# P09_USB_HOST_USB_OTG.net
KiCad netlist of a schematic drawn in Altium Designer
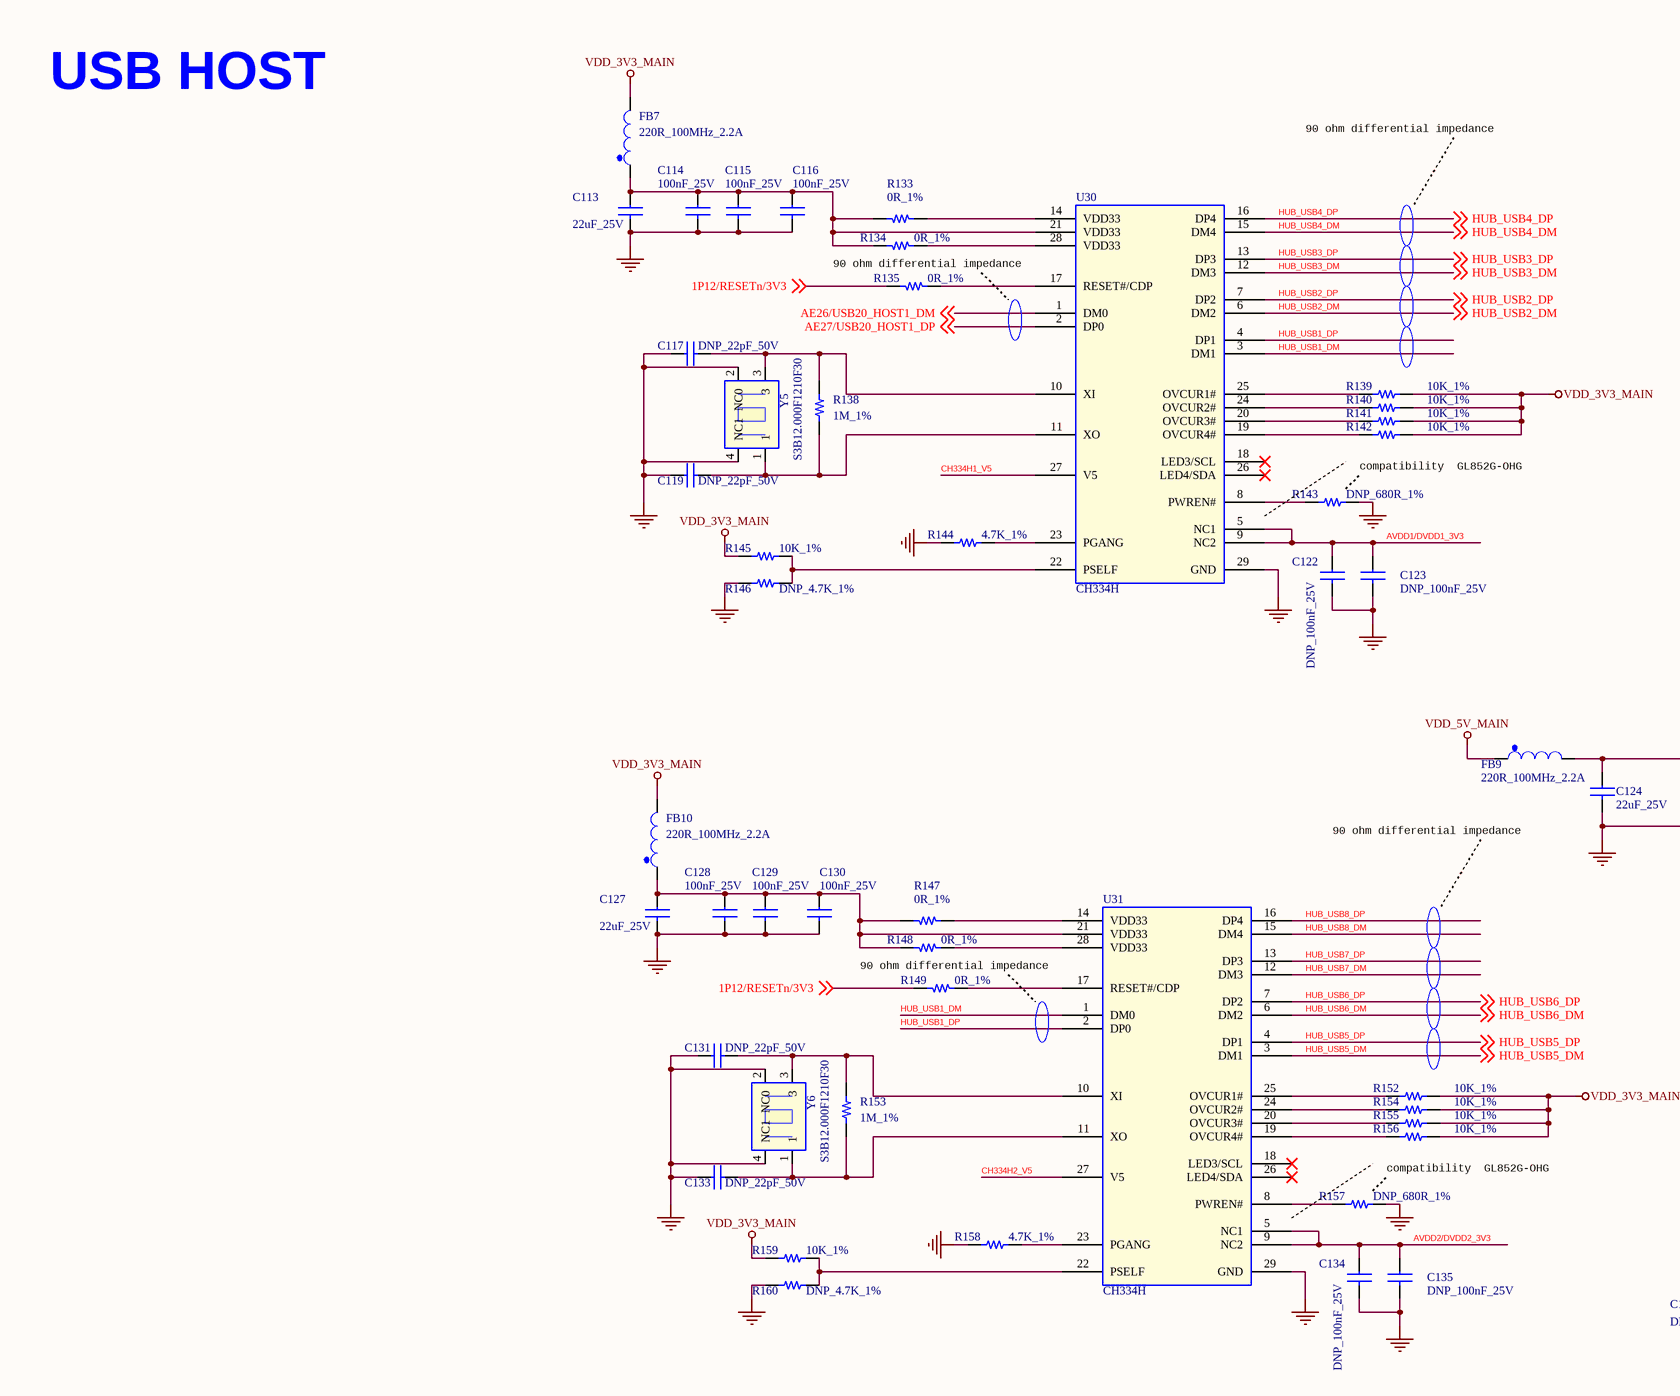
[diagram p0: P09_USB HOST_USB OTG.SchDoc, top left]
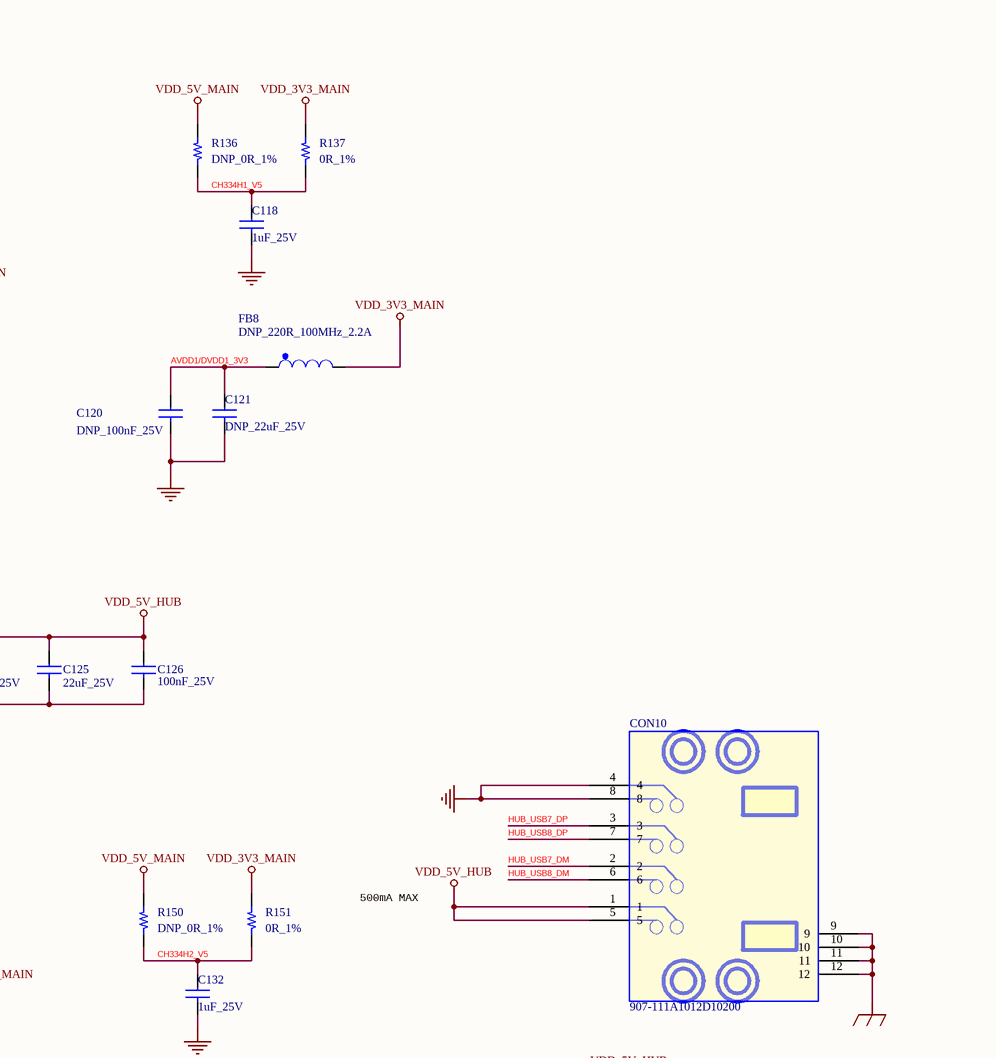
[diagram p1: P09_USB HOST_USB OTG.SchDoc, top right]
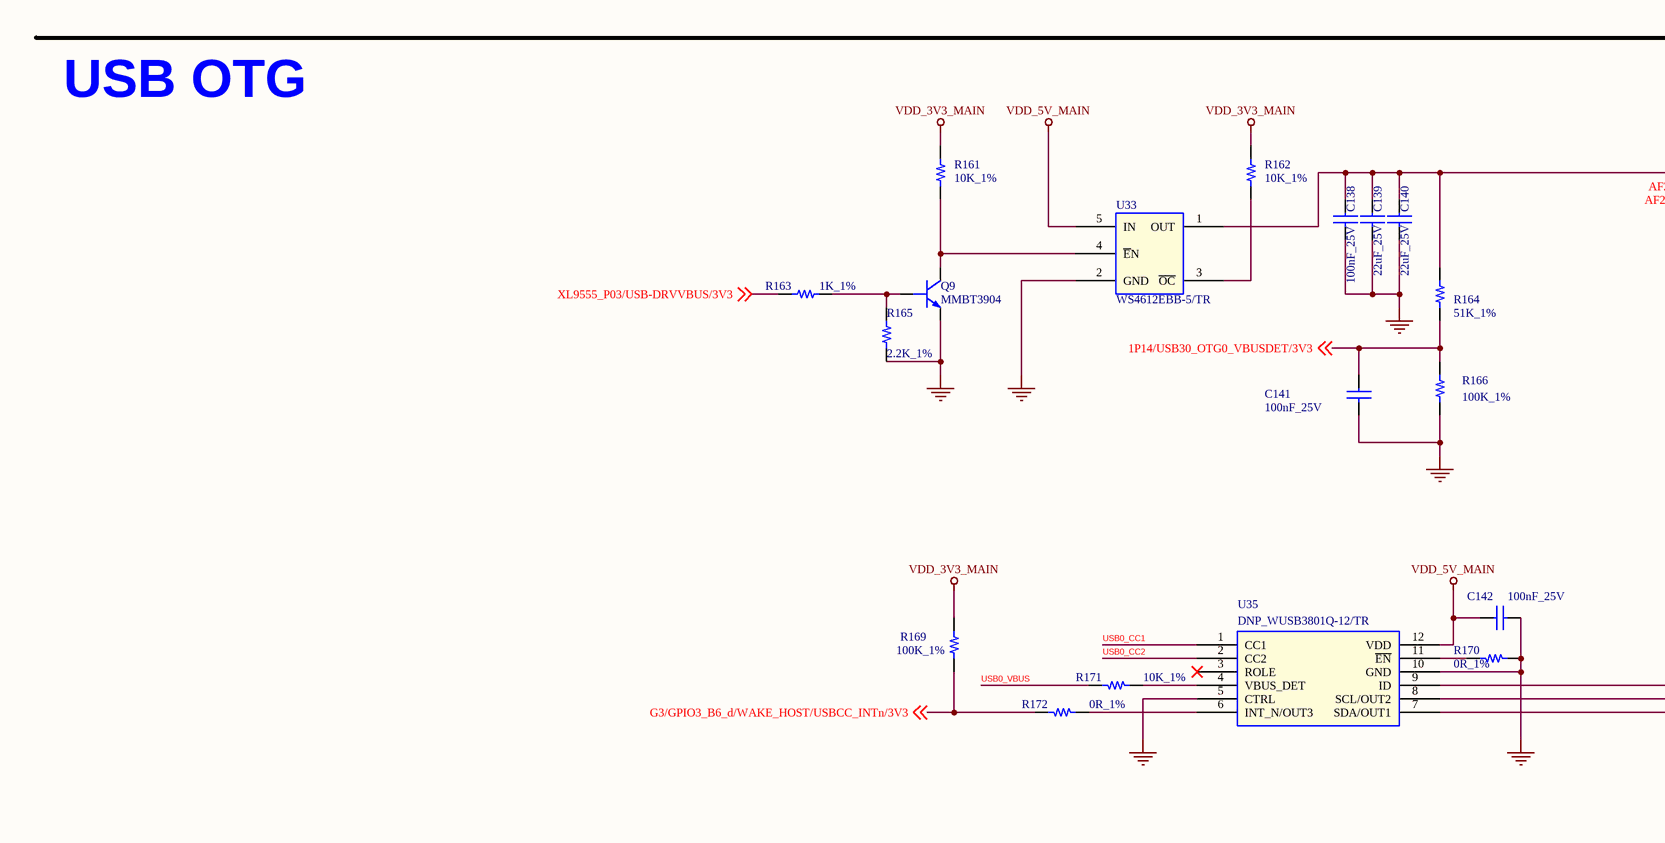
[diagram p2: P09_USB HOST_USB OTG.SchDoc, bottom left]
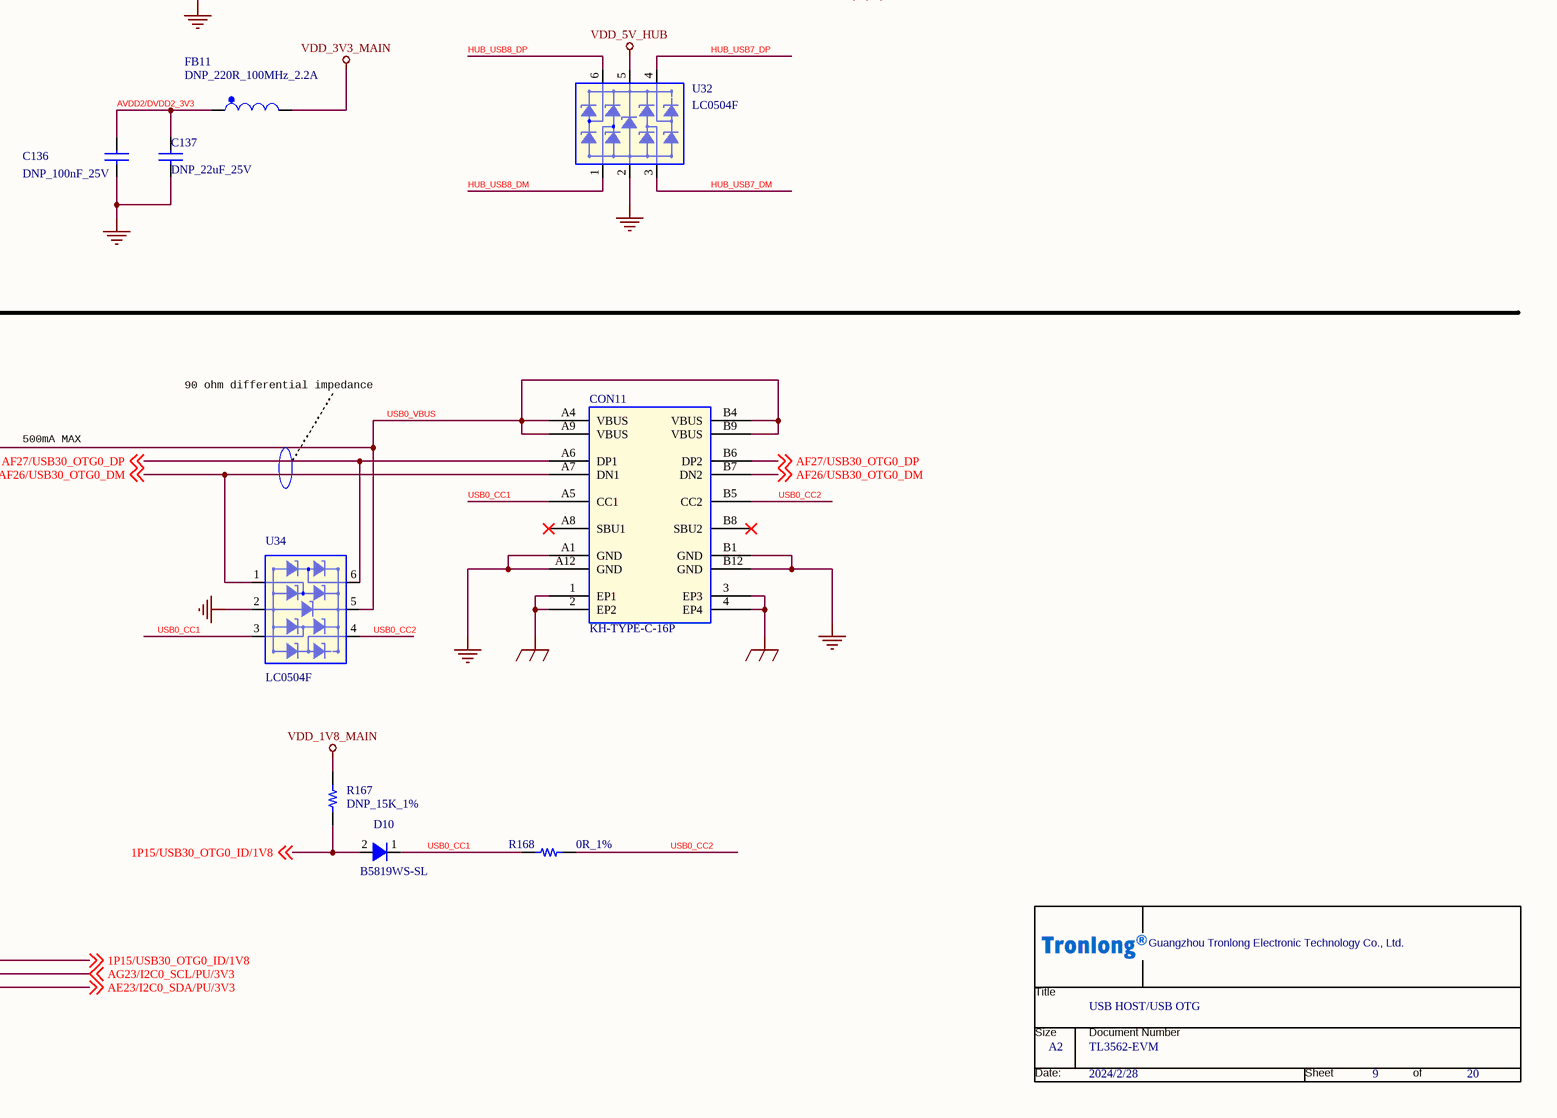
[diagram p3: P09_USB HOST_USB OTG.SchDoc, bottom right]

(export (version "E")
  (design (tool "Eeschema 10.0.6"))
  (components
    (comp (ref "C113")
      (value "22uF_25V")
      (footprint "C0805")
      (description "贴片陶瓷电容,22uF,20%,25V,X5R")
      (libsource (lib "*") (part "CAP NP_Dup3"))
    )
    (comp (ref "C114")
      (value "100nF_25V")
      (footprint "C0402")
      (description "贴片陶瓷电容,100nF,10%,25V,X5R")
      (libsource (lib "*") (part "CAP NP_Dup3"))
    )
    (comp (ref "C115")
      (value "100nF_25V")
      (footprint "C0402")
      (description "贴片陶瓷电容,100nF,10%,25V,X5R")
      (libsource (lib "*") (part "CAP NP_Dup3"))
    )
    (comp (ref "C116")
      (value "100nF_25V")
      (footprint "C0402")
      (description "贴片陶瓷电容,100nF,10%,25V,X5R")
      (libsource (lib "*") (part "CAP NP_Dup3"))
    )
    (comp (ref "C117")
      (value "DNP_22pF_50V")
      (footprint "C0603")
      (description "贴片陶瓷电容,22pF,5%,50V,COG")
      (libsource (lib "*") (part "CAP NP_Dup3"))
    )
    (comp (ref "C118")
      (value "1uF_25V")
      (footprint "C0603")
      (description "贴片陶瓷电容,1uF,10%,25V,X5R")
      (libsource (lib "*") (part "CAP NP_Dup3"))
    )
    (comp (ref "C119")
      (value "DNP_22pF_50V")
      (footprint "C0603")
      (description "贴片陶瓷电容,22pF,5%,50V,COG")
      (libsource (lib "*") (part "CAP NP_Dup3"))
    )
    (comp (ref "C120")
      (value "DNP_100nF_25V")
      (footprint "C0402")
      (description "100nF,10%,C0402,25V")
      (libsource (lib "*") (part "CAP NP_Dup3"))
    )
    (comp (ref "C121")
      (value "DNP_22uF_25V")
      (footprint "C0805")
      (description "贴片陶瓷电容,22uF,10%,16V,X5R")
      (libsource (lib "*") (part "CAP NP_Dup3"))
    )
    (comp (ref "C122")
      (value "DNP_100nF_25V")
      (footprint "C0402")
      (description "100nF,10%,C0402,25V")
      (libsource (lib "*") (part "CAP NP_Dup3"))
    )
    (comp (ref "C123")
      (value "DNP_100nF_25V")
      (footprint "C0402")
      (description "100nF,10%,C0402,25V")
      (libsource (lib "*") (part "CAP NP_Dup3"))
    )
    (comp (ref "C124")
      (value "22uF_25V")
      (footprint "C0805")
      (description "贴片陶瓷电容,22uF,20%,25V,X5R")
      (libsource (lib "*") (part "CAP NP_Dup3"))
    )
    (comp (ref "C125")
      (value "22uF_25V")
      (footprint "C0805")
      (description "贴片陶瓷电容,22uF,20%,25V,X5R")
      (libsource (lib "*") (part "CAP NP_Dup3"))
    )
    (comp (ref "C126")
      (value "100nF_25V")
      (footprint "C0402")
      (description "贴片陶瓷电容,100nF,10%,25V,X5R")
      (libsource (lib "*") (part "CAP NP_Dup3"))
    )
    (comp (ref "C127")
      (value "22uF_25V")
      (footprint "C0805")
      (description "贴片陶瓷电容,22uF,20%,25V,X5R")
      (libsource (lib "*") (part "CAP NP_Dup3"))
    )
    (comp (ref "C128")
      (value "100nF_25V")
      (footprint "C0402")
      (description "贴片陶瓷电容,100nF,10%,25V,X5R")
      (libsource (lib "*") (part "CAP NP_Dup3"))
    )
    (comp (ref "C129")
      (value "100nF_25V")
      (footprint "C0402")
      (description "贴片陶瓷电容,100nF,10%,25V,X5R")
      (libsource (lib "*") (part "CAP NP_Dup3"))
    )
    (comp (ref "C130")
      (value "100nF_25V")
      (footprint "C0402")
      (description "贴片陶瓷电容,100nF,10%,25V,X5R")
      (libsource (lib "*") (part "CAP NP_Dup3"))
    )
    (comp (ref "C131")
      (value "DNP_22pF_50V")
      (footprint "C0603")
      (description "贴片陶瓷电容,22pF,5%,50V,COG")
      (libsource (lib "*") (part "CAP NP_Dup3"))
    )
    (comp (ref "C132")
      (value "1uF_25V")
      (footprint "C0603")
      (description "贴片陶瓷电容,1uF,10%,25V,X5R")
      (libsource (lib "*") (part "CAP NP_Dup3"))
    )
    (comp (ref "C133")
      (value "DNP_22pF_50V")
      (footprint "C0603")
      (description "贴片陶瓷电容,22pF,5%,50V,COG")
      (libsource (lib "*") (part "CAP NP_Dup3"))
    )
    (comp (ref "C134")
      (value "DNP_100nF_25V")
      (footprint "C0402")
      (description "100nF,10%,C0402,25V")
      (libsource (lib "*") (part "CAP NP_Dup3"))
    )
    (comp (ref "C135")
      (value "DNP_100nF_25V")
      (footprint "C0402")
      (description "100nF,10%,C0402,25V")
      (libsource (lib "*") (part "CAP NP_Dup3"))
    )
    (comp (ref "C136")
      (value "DNP_100nF_25V")
      (footprint "C0402")
      (description "100nF,10%,C0402,25V")
      (libsource (lib "*") (part "CAP NP_Dup3"))
    )
    (comp (ref "C137")
      (value "DNP_22uF_25V")
      (footprint "C0805")
      (description "贴片陶瓷电容,22uF,10%,16V,X5R")
      (libsource (lib "*") (part "CAP NP_Dup3"))
    )
    (comp (ref "C138")
      (value "100nF_25V")
      (footprint "C0402")
      (description "贴片陶瓷电容,100nF,10%,25V,X5R")
      (libsource (lib "*") (part "CAP NP_Dup1"))
    )
    (comp (ref "C139")
      (value "22uF_25V")
      (footprint "C0805")
      (description "贴片陶瓷电容,22uF,20%,25V,X5R")
      (libsource (lib "*") (part "CAP NP_Dup1"))
    )
    (comp (ref "C140")
      (value "22uF_25V")
      (footprint "C0805")
      (description "贴片陶瓷电容,22uF,20%,25V,X5R")
      (libsource (lib "*") (part "CAP NP_Dup1"))
    )
    (comp (ref "C141")
      (value "100nF_25V")
      (footprint "C0402")
      (description "贴片陶瓷电容,100nF,10%,25V,X5R")
      (libsource (lib "*") (part "CAP NP_Dup1"))
    )
    (comp (ref "C142")
      (value "100nF_25V")
      (footprint "C0402")
      (description "贴片陶瓷电容,100nF,10%,25V,X5R")
      (libsource (lib "*") (part "CAP NP_Dup1"))
    )
    (comp (ref "CON10")
      (value "907-111A1012D10200")
      (footprint "CON_USBA_DUAL")
      (description "USB-A-双层座,8PIN,90度,母座,插件")
      (fields
        (field (name "MANUFACTURER PARTNUMBER") "FUS208-FDBW3K")
        (field (name "MANUFACTURER") "深圳特思嘉工业电子有限公司（TXGA）")
      )
      (libsource (lib "*") (part "DOUBLE USB A TYPE"))
    )
    (comp (ref "CON11")
      (value "KH-TYPE-C-16P")
      (footprint "TYPE-C_16P_90_SMD")
      (description "Type-C 母座 90度 16 Pin")
      (fields (field (name "MANUFACTURER") "深圳市金航标电子有限公司(kinghelm)"))
      (libsource (lib "*") (part "usb 3_0.0 type-c female"))
    )
    (comp (ref "D10")
      (value "B5819WS-SL")
      (footprint "SOD-323")
      (description "肖特基二极管,VR=40V,IF=1A,VF=0.6V@1A")
      (fields (field (name "TIINTPARTNUMBER") "1E0013") (field (name "MFR") "On Semiconductor"))
      (libsource (lib "*") (part "Diode200mA250V_2"))
    )
    (comp (ref "FB7")
      (value "220R_100MHz_2.2A")
      (footprint "L0603")
      (description "磁珠,50mΩ,2.2A,220R@100MHz")
      (fields
        (field (name "MANUFACTURER") "深圳顺络电子股份有限公司（Sunlord）")
        (field (name "MANUFACTURER PARTNUMBER") "UPZ1608U221-2R2TF")
      )
      (libsource (lib "*") (part "FERRITE BEAD_Dup1"))
    )
    (comp (ref "FB8")
      (value "DNP_220R_100MHz_2.2A")
      (footprint "L0603")
      (description "磁珠,50mΩ,2.2A,220R@100MHz")
      (fields
        (field (name "MANUFACTURER") "深圳顺络电子股份有限公司（Sunlord）")
        (field (name "MANUFACTURER PARTNUMBER") "UPZ1608U221-2R2TF")
      )
      (libsource (lib "*") (part "FERRITE BEAD_Dup1"))
    )
    (comp (ref "FB9")
      (value "220R_100MHz_2.2A")
      (footprint "L0603")
      (description "磁珠,50mΩ,2.2A,220R@100MHz")
      (fields
        (field (name "MANUFACTURER PARTNUMBER") "UPZ1608U221-2R2TF")
        (field (name "MANUFACTURER") "深圳顺络电子股份有限公司（Sunlord）")
      )
      (libsource (lib "*") (part "FERRITE BEAD_Dup1"))
    )
    (comp (ref "FB10")
      (value "220R_100MHz_2.2A")
      (footprint "L0603")
      (description "磁珠,50mΩ,2.2A,220R@100MHz")
      (fields
        (field (name "MANUFACTURER PARTNUMBER") "UPZ1608U221-2R2TF")
        (field (name "MANUFACTURER") "深圳顺络电子股份有限公司（Sunlord）")
      )
      (libsource (lib "*") (part "FERRITE BEAD_Dup1"))
    )
    (comp (ref "FB11")
      (value "DNP_220R_100MHz_2.2A")
      (footprint "L0603")
      (description "磁珠,50mΩ,2.2A,220R@100MHz")
      (fields
        (field (name "MANUFACTURER") "深圳顺络电子股份有限公司（Sunlord）")
        (field (name "MANUFACTURER PARTNUMBER") "UPZ1608U221-2R2TF")
      )
      (libsource (lib "*") (part "FERRITE BEAD_Dup1"))
    )
    (comp (ref "Q9")
      (value "MMBT3904")
      (footprint "SOT23-3_DBZ3")
      (description "BJT,NPN,Vceo=40V,Ic=200mA,fT=300MHz,PD=200mW")
      (fields (field (name "MANUFACTURER") "江苏长晶科技有限公司（JSCJ）"))
      (libsource (lib "*") (part "MMBT3904/SOT"))
    )
    (comp (ref "R133")
      (value "0R_1%")
      (footprint "R0402")
      (description "0R,±1%,R0402,≥1/16W")
      (libsource (lib "*") (part "Resistor_Dup3"))
    )
    (comp (ref "R134")
      (value "0R_1%")
      (footprint "R0402")
      (description "0R,±1%,R0402,≥1/16W")
      (libsource (lib "*") (part "Resistor_Dup3"))
    )
    (comp (ref "R135")
      (value "0R_1%")
      (footprint "R0402")
      (description "0R,±1%,R0402,≥1/16W")
      (libsource (lib "*") (part "Resistor_Dup3"))
    )
    (comp (ref "R136")
      (value "DNP_0R_1%")
      (footprint "R0603")
      (description "贴片电阻,0R,±1%,1/10W")
      (libsource (lib "*") (part "Resistor_Dup3"))
    )
    (comp (ref "R137")
      (value "0R_1%")
      (footprint "R0603")
      (description "0R,±1%,R0603,≥1/10W")
      (libsource (lib "*") (part "Resistor_Dup3"))
    )
    (comp (ref "R138")
      (value "1M_1%")
      (footprint "R0603")
      (description "贴片电阻,1M,±1%,1/10W")
      (libsource (lib "*") (part "Resistor_Dup3"))
    )
    (comp (ref "R139")
      (value "10K_1%")
      (footprint "R0402")
      (description "贴片电阻,10K,±1%,1/16W")
      (libsource (lib "*") (part "Resistor_Dup3"))
    )
    (comp (ref "R140")
      (value "10K_1%")
      (footprint "R0402")
      (description "贴片电阻,10K,±1%,1/16W")
      (libsource (lib "*") (part "Resistor_Dup3"))
    )
    (comp (ref "R141")
      (value "10K_1%")
      (footprint "R0402")
      (description "贴片电阻,10K,±1%,1/16W")
      (libsource (lib "*") (part "Resistor_Dup3"))
    )
    (comp (ref "R142")
      (value "10K_1%")
      (footprint "R0402")
      (description "贴片电阻,10K,±1%,1/16W")
      (libsource (lib "*") (part "Resistor_Dup3"))
    )
    (comp (ref "R143")
      (value "DNP_680R_1%")
      (footprint "R0603")
      (description "贴片电阻,680R,±1%,1/10W")
      (libsource (lib "*") (part "Resistor_Dup3"))
    )
    (comp (ref "R144")
      (value "4.7K_1%")
      (footprint "R0402")
      (description "贴片电阻,4.7K,±1%,1/16W")
      (libsource (lib "*") (part "Resistor_Dup3"))
    )
    (comp (ref "R145")
      (value "10K_1%")
      (footprint "R0402")
      (description "贴片电阻,10K,±1%,1/16W")
      (libsource (lib "*") (part "Resistor_Dup3"))
    )
    (comp (ref "R146")
      (value "DNP_4.7K_1%")
      (footprint "R0402")
      (description "贴片电阻,4.7K,±1%,1/16W")
      (libsource (lib "*") (part "Resistor_Dup3"))
    )
    (comp (ref "R147")
      (value "0R_1%")
      (footprint "R0402")
      (description "0R,±1%,R0402,≥1/16W")
      (libsource (lib "*") (part "Resistor_Dup3"))
    )
    (comp (ref "R148")
      (value "0R_1%")
      (footprint "R0402")
      (description "0R,±1%,R0402,≥1/16W")
      (libsource (lib "*") (part "Resistor_Dup3"))
    )
    (comp (ref "R149")
      (value "0R_1%")
      (footprint "R0402")
      (description "0R,±1%,R0402,≥1/16W")
      (libsource (lib "*") (part "Resistor_Dup3"))
    )
    (comp (ref "R150")
      (value "DNP_0R_1%")
      (footprint "R0603")
      (description "贴片电阻,0R,±1%,1/10W")
      (libsource (lib "*") (part "Resistor_Dup3"))
    )
    (comp (ref "R151")
      (value "0R_1%")
      (footprint "R0603")
      (description "0R,±1%,R0603,≥1/10W")
      (libsource (lib "*") (part "Resistor_Dup3"))
    )
    (comp (ref "R152")
      (value "10K_1%")
      (footprint "R0402")
      (description "贴片电阻,10K,±1%,1/16W")
      (libsource (lib "*") (part "Resistor_Dup3"))
    )
    (comp (ref "R153")
      (value "1M_1%")
      (footprint "R0603")
      (description "贴片电阻,1M,±1%,1/10W")
      (libsource (lib "*") (part "Resistor_Dup3"))
    )
    (comp (ref "R154")
      (value "10K_1%")
      (footprint "R0402")
      (description "贴片电阻,10K,±1%,1/16W")
      (libsource (lib "*") (part "Resistor_Dup3"))
    )
    (comp (ref "R155")
      (value "10K_1%")
      (footprint "R0402")
      (description "贴片电阻,10K,±1%,1/16W")
      (libsource (lib "*") (part "Resistor_Dup3"))
    )
    (comp (ref "R156")
      (value "10K_1%")
      (footprint "R0402")
      (description "贴片电阻,10K,±1%,1/16W")
      (libsource (lib "*") (part "Resistor_Dup3"))
    )
    (comp (ref "R157")
      (value "DNP_680R_1%")
      (footprint "R0603")
      (description "贴片电阻,680R,±1%,1/10W")
      (libsource (lib "*") (part "Resistor_Dup3"))
    )
    (comp (ref "R158")
      (value "4.7K_1%")
      (footprint "R0402")
      (description "贴片电阻,4.7K,±1%,1/16W")
      (libsource (lib "*") (part "Resistor_Dup3"))
    )
    (comp (ref "R159")
      (value "10K_1%")
      (footprint "R0402")
      (description "贴片电阻,10K,±1%,1/16W")
      (libsource (lib "*") (part "Resistor_Dup3"))
    )
    (comp (ref "R160")
      (value "DNP_4.7K_1%")
      (footprint "R0402")
      (description "贴片电阻,4.7K,±1%,1/16W")
      (libsource (lib "*") (part "Resistor_Dup3"))
    )
    (comp (ref "R161")
      (value "10K_1%")
      (footprint "R0402")
      (description "贴片电阻,10K,±1%,1/16W")
      (libsource (lib "*") (part "R 1%"))
    )
    (comp (ref "R162")
      (value "10K_1%")
      (footprint "R0402")
      (description "贴片电阻,10K,±1%,1/16W")
      (libsource (lib "*") (part "R 1%"))
    )
    (comp (ref "R163")
      (value "1K_1%")
      (footprint "R0402")
      (description "贴片电阻,1K,±1%,1/16W")
      (libsource (lib "*") (part "Resistor_Dup3"))
    )
    (comp (ref "R164")
      (value "51K_1%")
      (footprint "R0402")
      (description "贴片电阻,51K,±1%,1/16W")
      (fields
        (field (name "MISTRAL PART NO") "110009031036-R")
        (field (name "MFR_PART_NUMBER") "ERJ-2RNF6981V")
      )
      (libsource (lib "*") (part "R 1%"))
    )
    (comp (ref "R165")
      (value "2.2K_1%")
      (footprint "R0603")
      (description "贴片电阻,2.2K,±1%,1/10W")
      (libsource (lib "*") (part "Resistor_Dup3"))
    )
    (comp (ref "R166")
      (value "100K_1%")
      (footprint "R0402")
      (description "贴片电阻,100K,±1%,1/16W")
      (libsource (lib "*") (part "R 1%"))
    )
    (comp (ref "R167")
      (value "DNP_15K_1%")
      (footprint "R0402")
      (description "贴片电阻,15K,±1%,1/16W")
      (libsource (lib "*") (part "R 1%"))
    )
    (comp (ref "R168")
      (value "0R_1%")
      (footprint "R0402")
      (description "0R,±1%,R0402,≥1/16W")
      (libsource (lib "*") (part "10_R_0"))
    )
    (comp (ref "R169")
      (value "100K_1%")
      (footprint "R0402")
      (description "贴片电阻,100K,±1%,1/16W")
      (libsource (lib "*") (part "R 1%"))
    )
    (comp (ref "R170")
      (value "0R_1%")
      (footprint "R0402")
      (description "0R,±1%,R0402,≥1/16W")
      (libsource (lib "*") (part "R 1%"))
    )
    (comp (ref "R171")
      (value "10K_1%")
      (footprint "R0402")
      (description "贴片电阻,10K,±1%,1/16W")
      (libsource (lib "*") (part "R 1%"))
    )
    (comp (ref "R172")
      (value "0R_1%")
      (footprint "R0402")
      (description "0R,±1%,R0402,≥1/16W")
      (libsource (lib "*") (part "R 1%"))
    )
    (comp (ref "U30")
      (value "CH334H")
      (footprint "QFN28_5x5")
      (description "USB HUB控制器")
      (fields (field (name "MANUFACTURER") "南京沁恒微电子股份有限公司（WCH）"))
      (libsource (lib "*") (part "GL852GT_1"))
    )
    (comp (ref "U31")
      (value "CH334H")
      (footprint "QFN28_5x5")
      (description "USB HUB控制器")
      (fields (field (name "MANUFACTURER") "南京沁恒微电子股份有限公司（WCH）"))
      (libsource (lib "*") (part "GL852GT_1"))
    )
    (comp (ref "U32")
      (value "LC0504F")
      (footprint "SOT363")
      (description "ESD二极管,VRWM=5V,VBR=6V,四组,单向,8KV,15KV")
      (fields (field (name "MANUFACTURER") "上海雷卯电子科技有限公司（Leiditech）"))
      (libsource (lib "*") (part "PRTR5V0U4Y"))
    )
    (comp (ref "U33")
      (value "WS4612EBB-5/TR")
      (footprint "SOT23-5")
      (description "限流配电开关,2.5V~5.5V,1.4A")
      (fields (field (name "MANUFACTURER") "上海韦尔半导体股份有限公司（WILLSEMI）"))
      (libsource (lib "*") (part "TPS2041BDGN_0"))
    )
    (comp (ref "U34")
      (value "LC0504F")
      (footprint "SOT363")
      (description "ESD二极管,VRWM=5V,VBR=6V,四组,单向,8KV,15KV")
      (fields (field (name "MANUFACTURER") "上海雷卯电子科技有限公司（Leiditech）"))
      (libsource (lib "*") (part "PRTR5V0U4Y"))
    )
    (comp (ref "U35")
      (value "DNP_WUSB3801Q-12/TR")
      (footprint "QFN1616-12L")
      (description "USB Type-C配置通道适配器芯片")
      (fields
        (field (name "MANUFACTURER PARTNUMBER") "WUSB3801Q-12/TR")
        (field (name "MANUFACTURER") "上海韦尔半导体股份有限公司（WILLSEMI）")
      )
      (libsource (lib "*") (part "TPS54286PWP_2"))
    )
    (comp (ref "Y5")
      (value "S3B12.000F1210F30")
      (footprint "SMD_3225")
      (description "四脚无源晶振,12MHz,±10ppm,12pF,100Ω,±30ppm")
      (fields (field (name "MANUFACTURER") "深圳市星通时频电子有限公司公司（JSCJ）"))
      (libsource (lib "*") (part "CRYSTAL"))
    )
    (comp (ref "Y6")
      (value "S3B12.000F1210F30")
      (footprint "SMD_3225")
      (description "四脚无源晶振,12MHz,±10ppm,12pF,100Ω,±30ppm")
      (fields (field (name "MANUFACTURER") "深圳市星通时频电子有限公司公司（JSCJ）"))
      (libsource (lib "*") (part "CRYSTAL"))
    )
  )
  (nets
    (net (code "1") (name "/AVDD1{slash}DVDD1_3V3") (class "Default")
      (node (ref "C120") (pin "1") (pinfunction "1_1") (pintype "passive"))
      (node (ref "C121") (pin "1") (pinfunction "1_1") (pintype "passive"))
      (node (ref "C122") (pin "1") (pinfunction "1_1") (pintype "passive"))
      (node (ref "C123") (pin "1") (pinfunction "1_1") (pintype "passive"))
      (node (ref "FB8") (pin "1") (pinfunction "1_1") (pintype "passive"))
      (node (ref "U30") (pin "5") (pinfunction "NC1_5") (pintype "passive"))
      (node (ref "U30") (pin "9") (pinfunction "NC2_9") (pintype "passive"))
    )
    (net (code "2") (name "/AVDD2{slash}DVDD2_3V3") (class "Default")
      (node (ref "C134") (pin "1") (pinfunction "1_1") (pintype "passive"))
      (node (ref "C135") (pin "1") (pinfunction "1_1") (pintype "passive"))
      (node (ref "C136") (pin "1") (pinfunction "1_1") (pintype "passive"))
      (node (ref "C137") (pin "1") (pinfunction "1_1") (pintype "passive"))
      (node (ref "FB11") (pin "1") (pinfunction "1_1") (pintype "passive"))
      (node (ref "U31") (pin "5") (pinfunction "NC1_5") (pintype "passive"))
      (node (ref "U31") (pin "9") (pinfunction "NC2_9") (pintype "passive"))
    )
    (net (code "3") (name "/CH334H1_V5") (class "Default")
      (node (ref "C118") (pin "1") (pinfunction "1_1") (pintype "passive"))
      (node (ref "R136") (pin "1") (pinfunction "1_1") (pintype "passive"))
      (node (ref "R137") (pin "1") (pinfunction "1_1") (pintype "passive"))
      (node (ref "U30") (pin "27") (pinfunction "V5_27") (pintype "passive"))
    )
    (net (code "4") (name "/CH334H2_V5") (class "Default")
      (node (ref "C132") (pin "1") (pinfunction "1_1") (pintype "passive"))
      (node (ref "R150") (pin "1") (pinfunction "1_1") (pintype "passive"))
      (node (ref "R151") (pin "1") (pinfunction "1_1") (pintype "passive"))
      (node (ref "U31") (pin "27") (pinfunction "V5_27") (pintype "passive"))
    )
    (net (code "5") (name "/HUB_USB1_DM") (class "Default")
      (node (ref "U30") (pin "3") (pinfunction "DM1_3") (pintype "passive"))
      (node (ref "U31") (pin "1") (pinfunction "DM0_1") (pintype "passive"))
    )
    (net (code "6") (name "/HUB_USB1_DP") (class "Default")
      (node (ref "U30") (pin "4") (pinfunction "DP1_4") (pintype "passive"))
      (node (ref "U31") (pin "2") (pinfunction "DP0_2") (pintype "passive"))
    )
    (net (code "7") (name "/HUB_USB7_DM") (class "Default")
      (node (ref "CON10") (pin "2") (pinfunction "2_2") (pintype "passive"))
      (node (ref "U31") (pin "12") (pinfunction "DM3_12") (pintype "passive"))
      (node (ref "U32") (pin "3") (pinfunction "3_3") (pintype "passive"))
    )
    (net (code "8") (name "/HUB_USB7_DP") (class "Default")
      (node (ref "CON10") (pin "3") (pinfunction "3_3") (pintype "passive"))
      (node (ref "U31") (pin "13") (pinfunction "DP3_13") (pintype "passive"))
      (node (ref "U32") (pin "4") (pinfunction "4_4") (pintype "passive"))
    )
    (net (code "9") (name "/HUB_USB8_DM") (class "Default")
      (node (ref "CON10") (pin "6") (pinfunction "6_6") (pintype "passive"))
      (node (ref "U31") (pin "15") (pinfunction "DM4_15") (pintype "passive"))
      (node (ref "U32") (pin "1") (pinfunction "1_1") (pintype "passive"))
    )
    (net (code "10") (name "/HUB_USB8_DP") (class "Default")
      (node (ref "CON10") (pin "7") (pinfunction "7_7") (pintype "passive"))
      (node (ref "U31") (pin "16") (pinfunction "DP4_16") (pintype "passive"))
      (node (ref "U32") (pin "6") (pinfunction "6_6") (pintype "passive"))
    )
    (net (code "11") (name "/USB0_CC1") (class "Default")
      (node (ref "CON11") (pin "A5") (pinfunction "CC1_A5") (pintype "passive"))
      (node (ref "D10") (pin "1") (pinfunction "Anode_1") (pintype "passive"))
      (node (ref "R168") (pin "2") (pinfunction "2_2") (pintype "passive"))
      (node (ref "U34") (pin "3") (pinfunction "3_3") (pintype "passive"))
      (node (ref "U35") (pin "1") (pinfunction "CC1_1") (pintype "passive"))
    )
    (net (code "12") (name "/USB0_CC2") (class "Default")
      (node (ref "CON11") (pin "B5") (pinfunction "CC2_B5") (pintype "passive"))
      (node (ref "R168") (pin "1") (pinfunction "1_1") (pintype "passive"))
      (node (ref "U34") (pin "4") (pinfunction "4_4") (pintype "passive"))
      (node (ref "U35") (pin "2") (pinfunction "CC2_2") (pintype "passive"))
    )
    (net (code "13") (name "/USB0_VBUS") (class "Default")
      (node (ref "C138") (pin "1") (pinfunction "1_1") (pintype "passive"))
      (node (ref "C139") (pin "1") (pinfunction "1_1") (pintype "passive"))
      (node (ref "C140") (pin "1") (pinfunction "1_1") (pintype "passive"))
      (node (ref "CON11") (pin "A4") (pinfunction "VBUS_A4") (pintype "power_in"))
      (node (ref "CON11") (pin "A9") (pinfunction "VBUS_A9") (pintype "power_in"))
      (node (ref "CON11") (pin "B4") (pinfunction "VBUS_B4") (pintype "power_in"))
      (node (ref "CON11") (pin "B9") (pinfunction "VBUS_B9") (pintype "power_in"))
      (node (ref "R164") (pin "2") (pinfunction "2_2") (pintype "passive"))
      (node (ref "R171") (pin "2") (pinfunction "2_2") (pintype "passive"))
      (node (ref "U33") (pin "1") (pinfunction "OUT_1") (pintype "passive"))
      (node (ref "U34") (pin "5") (pinfunction "5_5") (pintype "passive"))
    )
    (net (code "14") (name "1P12{slash}RESETn{slash}3V3") (class "Default")
      (node (ref "R135") (pin "2") (pinfunction "2_2") (pintype "passive"))
      (node (ref "R149") (pin "2") (pinfunction "2_2") (pintype "passive"))
    )
    (net (code "15") (name "1P14{slash}USB30_OTG0_VBUSDET{slash}3V3") (class "Default")
      (node (ref "C141") (pin "1") (pinfunction "1_1") (pintype "passive"))
      (node (ref "R164") (pin "1") (pinfunction "1_1") (pintype "passive"))
      (node (ref "R166") (pin "2") (pinfunction "2_2") (pintype "passive"))
    )
    (net (code "16") (name "1P15{slash}USB30_OTG0_ID{slash}1V8") (class "Default")
      (node (ref "D10") (pin "2") (pinfunction "Cathode_2") (pintype "passive"))
      (node (ref "R167") (pin "2") (pinfunction "2_2") (pintype "passive"))
      (node (ref "U35") (pin "9") (pinfunction "ID_9") (pintype "passive"))
    )
    (net (code "17") (name "AE23{slash}I2C0_SDA{slash}PU{slash}3V3") (class "Default")
      (node (ref "U35") (pin "7") (pinfunction "SDA/OUT1_7") (pintype "passive"))
    )
    (net (code "18") (name "AE26{slash}USB20_HOST1_DM") (class "Default")
      (node (ref "U30") (pin "1") (pinfunction "DM0_1") (pintype "passive"))
    )
    (net (code "19") (name "AE27{slash}USB20_HOST1_DP") (class "Default")
      (node (ref "U30") (pin "2") (pinfunction "DP0_2") (pintype "passive"))
    )
    (net (code "20") (name "AF26{slash}USB30_OTG0_DM") (class "Default")
      (node (ref "CON11") (pin "A7") (pinfunction "DN1_A7") (pintype "passive"))
      (node (ref "CON11") (pin "B7") (pinfunction "DN2_B7") (pintype "passive"))
      (node (ref "U34") (pin "1") (pinfunction "1_1") (pintype "passive"))
    )
    (net (code "21") (name "AF27{slash}USB30_OTG0_DP") (class "Default")
      (node (ref "CON11") (pin "A6") (pinfunction "DP1_A6") (pintype "passive"))
      (node (ref "CON11") (pin "B6") (pinfunction "DP2_B6") (pintype "passive"))
      (node (ref "U34") (pin "6") (pinfunction "6_6") (pintype "passive"))
    )
    (net (code "22") (name "AG23{slash}I2C0_SCL{slash}PU{slash}3V3") (class "Default")
      (node (ref "U35") (pin "8") (pinfunction "SCL/OUT2_8") (pintype "passive"))
    )
    (net (code "23") (name "EGND") (class "Default")
      (node (ref "CON10") (pin "10") (pinfunction "10_10") (pintype "passive"))
      (node (ref "CON10") (pin "11") (pinfunction "11_11") (pintype "passive"))
      (node (ref "CON10") (pin "12") (pinfunction "12_12") (pintype "passive"))
      (node (ref "CON10") (pin "9") (pinfunction "9_9") (pintype "passive"))
      (node (ref "CON11") (pin "1") (pinfunction "EP1_1") (pintype "power_in"))
      (node (ref "CON11") (pin "2") (pinfunction "EP2_2") (pintype "power_in"))
      (node (ref "CON11") (pin "3") (pinfunction "EP3_3") (pintype "power_in"))
      (node (ref "CON11") (pin "4") (pinfunction "EP4_4") (pintype "power_in"))
    )
    (net (code "24") (name "G3{slash}GPIO3_B6_d{slash}WAKE_HOST{slash}USBCC_INTn{slash}3V3") (class "Default")
      (node (ref "R169") (pin "2") (pinfunction "2_2") (pintype "passive"))
      (node (ref "R172") (pin "2") (pinfunction "2_2") (pintype "passive"))
    )
    (net (code "25") (name "GND") (class "Default")
      (node (ref "C113") (pin "2") (pinfunction "2_2") (pintype "passive"))
      (node (ref "C114") (pin "2") (pinfunction "2_2") (pintype "passive"))
      (node (ref "C115") (pin "2") (pinfunction "2_2") (pintype "passive"))
      (node (ref "C116") (pin "2") (pinfunction "2_2") (pintype "passive"))
      (node (ref "C117") (pin "1") (pinfunction "1_1") (pintype "passive"))
      (node (ref "C118") (pin "2") (pinfunction "2_2") (pintype "passive"))
      (node (ref "C119") (pin "1") (pinfunction "1_1") (pintype "passive"))
      (node (ref "C120") (pin "2") (pinfunction "2_2") (pintype "passive"))
      (node (ref "C121") (pin "2") (pinfunction "2_2") (pintype "passive"))
      (node (ref "C122") (pin "2") (pinfunction "2_2") (pintype "passive"))
      (node (ref "C123") (pin "2") (pinfunction "2_2") (pintype "passive"))
      (node (ref "C124") (pin "2") (pinfunction "2_2") (pintype "passive"))
      (node (ref "C125") (pin "2") (pinfunction "2_2") (pintype "passive"))
      (node (ref "C126") (pin "2") (pinfunction "2_2") (pintype "passive"))
      (node (ref "C127") (pin "2") (pinfunction "2_2") (pintype "passive"))
      (node (ref "C128") (pin "2") (pinfunction "2_2") (pintype "passive"))
      (node (ref "C129") (pin "2") (pinfunction "2_2") (pintype "passive"))
      (node (ref "C130") (pin "2") (pinfunction "2_2") (pintype "passive"))
      (node (ref "C131") (pin "1") (pinfunction "1_1") (pintype "passive"))
      (node (ref "C132") (pin "2") (pinfunction "2_2") (pintype "passive"))
      (node (ref "C133") (pin "1") (pinfunction "1_1") (pintype "passive"))
      (node (ref "C134") (pin "2") (pinfunction "2_2") (pintype "passive"))
      (node (ref "C135") (pin "2") (pinfunction "2_2") (pintype "passive"))
      (node (ref "C136") (pin "2") (pinfunction "2_2") (pintype "passive"))
      (node (ref "C137") (pin "2") (pinfunction "2_2") (pintype "passive"))
      (node (ref "C138") (pin "2") (pinfunction "2_2") (pintype "passive"))
      (node (ref "C139") (pin "2") (pinfunction "2_2") (pintype "passive"))
      (node (ref "C140") (pin "2") (pinfunction "2_2") (pintype "passive"))
      (node (ref "C141") (pin "2") (pinfunction "2_2") (pintype "passive"))
      (node (ref "C142") (pin "2") (pinfunction "2_2") (pintype "passive"))
      (node (ref "CON10") (pin "4") (pinfunction "4_4") (pintype "passive"))
      (node (ref "CON10") (pin "8") (pinfunction "8_8") (pintype "passive"))
      (node (ref "CON11") (pin "A1") (pinfunction "GND_A1") (pintype "power_in"))
      (node (ref "CON11") (pin "A12") (pinfunction "GND_A12") (pintype "power_in"))
      (node (ref "CON11") (pin "B1") (pinfunction "GND_B1") (pintype "power_in"))
      (node (ref "CON11") (pin "B12") (pinfunction "GND_B12") (pintype "power_in"))
      (node (ref "Q9") (pin "2") (pinfunction "E_2") (pintype "passive"))
      (node (ref "R143") (pin "2") (pinfunction "2_2") (pintype "passive"))
      (node (ref "R144") (pin "2") (pinfunction "2_2") (pintype "passive"))
      (node (ref "R146") (pin "2") (pinfunction "2_2") (pintype "passive"))
      (node (ref "R157") (pin "2") (pinfunction "2_2") (pintype "passive"))
      (node (ref "R158") (pin "2") (pinfunction "2_2") (pintype "passive"))
      (node (ref "R160") (pin "2") (pinfunction "2_2") (pintype "passive"))
      (node (ref "R165") (pin "1") (pinfunction "1_1") (pintype "passive"))
      (node (ref "R166") (pin "1") (pinfunction "1_1") (pintype "passive"))
      (node (ref "R170") (pin "1") (pinfunction "1_1") (pintype "passive"))
      (node (ref "U30") (pin "29") (pinfunction "GND_29") (pintype "power_in"))
      (node (ref "U31") (pin "29") (pinfunction "GND_29") (pintype "power_in"))
      (node (ref "U32") (pin "2") (pinfunction "2_2") (pintype "passive"))
      (node (ref "U33") (pin "2") (pinfunction "GND_2") (pintype "passive"))
      (node (ref "U34") (pin "2") (pinfunction "2_2") (pintype "passive"))
      (node (ref "U35") (pin "10") (pinfunction "GND_10") (pintype "power_in"))
      (node (ref "U35") (pin "5") (pinfunction "CTRL_5") (pintype "passive"))
      (node (ref "Y5") (pin "2") (pinfunction "NC0_2") (pintype "passive"))
      (node (ref "Y5") (pin "4") (pinfunction "NC1_4") (pintype "passive"))
      (node (ref "Y6") (pin "2") (pinfunction "NC0_2") (pintype "passive"))
      (node (ref "Y6") (pin "4") (pinfunction "NC1_4") (pintype "passive"))
    )
    (net (code "26") (name "HUB_USB2_DM") (class "Default")
      (node (ref "U30") (pin "6") (pinfunction "DM2_6") (pintype "passive"))
    )
    (net (code "27") (name "HUB_USB2_DP") (class "Default")
      (node (ref "U30") (pin "7") (pinfunction "DP2_7") (pintype "passive"))
    )
    (net (code "28") (name "HUB_USB3_DM") (class "Default")
      (node (ref "U30") (pin "12") (pinfunction "DM3_12") (pintype "passive"))
    )
    (net (code "29") (name "HUB_USB3_DP") (class "Default")
      (node (ref "U30") (pin "13") (pinfunction "DP3_13") (pintype "passive"))
    )
    (net (code "30") (name "HUB_USB4_DM") (class "Default")
      (node (ref "U30") (pin "15") (pinfunction "DM4_15") (pintype "passive"))
    )
    (net (code "31") (name "HUB_USB4_DP") (class "Default")
      (node (ref "U30") (pin "16") (pinfunction "DP4_16") (pintype "passive"))
    )
    (net (code "32") (name "HUB_USB5_DM") (class "Default")
      (node (ref "U31") (pin "3") (pinfunction "DM1_3") (pintype "passive"))
    )
    (net (code "33") (name "HUB_USB5_DP") (class "Default")
      (node (ref "U31") (pin "4") (pinfunction "DP1_4") (pintype "passive"))
    )
    (net (code "34") (name "HUB_USB6_DM") (class "Default")
      (node (ref "U31") (pin "6") (pinfunction "DM2_6") (pintype "passive"))
    )
    (net (code "35") (name "HUB_USB6_DP") (class "Default")
      (node (ref "U31") (pin "7") (pinfunction "DP2_7") (pintype "passive"))
    )
    (net (code "36") (name "Net-(C113-Pad1)") (class "Default")
      (node (ref "C113") (pin "1") (pinfunction "1_1") (pintype "passive"))
      (node (ref "C114") (pin "1") (pinfunction "1_1") (pintype "passive"))
      (node (ref "C115") (pin "1") (pinfunction "1_1") (pintype "passive"))
      (node (ref "C116") (pin "1") (pinfunction "1_1") (pintype "passive"))
      (node (ref "FB7") (pin "1") (pinfunction "1_1") (pintype "passive"))
      (node (ref "R133") (pin "1") (pinfunction "1_1") (pintype "passive"))
      (node (ref "R134") (pin "1") (pinfunction "1_1") (pintype "passive"))
      (node (ref "U30") (pin "21") (pinfunction "VDD33_21") (pintype "power_in"))
    )
    (net (code "37") (name "Net-(C127-Pad1)") (class "Default")
      (node (ref "C127") (pin "1") (pinfunction "1_1") (pintype "passive"))
      (node (ref "C128") (pin "1") (pinfunction "1_1") (pintype "passive"))
      (node (ref "C129") (pin "1") (pinfunction "1_1") (pintype "passive"))
      (node (ref "C130") (pin "1") (pinfunction "1_1") (pintype "passive"))
      (node (ref "FB10") (pin "1") (pinfunction "1_1") (pintype "passive"))
      (node (ref "R147") (pin "1") (pinfunction "1_1") (pintype "passive"))
      (node (ref "R148") (pin "1") (pinfunction "1_1") (pintype "passive"))
      (node (ref "U31") (pin "21") (pinfunction "VDD33_21") (pintype "power_in"))
    )
    (net (code "38") (name "Net-(Q9-B)") (class "Default")
      (node (ref "Q9") (pin "1") (pinfunction "B_1") (pintype "passive"))
      (node (ref "R163") (pin "1") (pinfunction "1_1") (pintype "passive"))
      (node (ref "R165") (pin "2") (pinfunction "2_2") (pintype "passive"))
    )
    (net (code "39") (name "Net-(Q9-C)") (class "Default")
      (node (ref "Q9") (pin "3") (pinfunction "C_3") (pintype "passive"))
      (node (ref "R161") (pin "2") (pinfunction "2_2") (pintype "passive"))
      (node (ref "U33") (pin "4") (pinfunction "~{E}N_4") (pintype "passive"))
    )
    (net (code "40") (name "Net-(R133-Pad2)") (class "Default")
      (node (ref "R133") (pin "2") (pinfunction "2_2") (pintype "passive"))
      (node (ref "U30") (pin "14") (pinfunction "VDD33_14") (pintype "power_in"))
    )
    (net (code "41") (name "Net-(R134-Pad2)") (class "Default")
      (node (ref "R134") (pin "2") (pinfunction "2_2") (pintype "passive"))
      (node (ref "U30") (pin "28") (pinfunction "VDD33_28") (pintype "power_in"))
    )
    (net (code "42") (name "Net-(R147-Pad2)") (class "Default")
      (node (ref "R147") (pin "2") (pinfunction "2_2") (pintype "passive"))
      (node (ref "U31") (pin "14") (pinfunction "VDD33_14") (pintype "power_in"))
    )
    (net (code "43") (name "Net-(R148-Pad2)") (class "Default")
      (node (ref "R148") (pin "2") (pinfunction "2_2") (pintype "passive"))
      (node (ref "U31") (pin "28") (pinfunction "VDD33_28") (pintype "power_in"))
    )
    (net (code "44") (name "Net-(U30-OVCUR1#)") (class "Default")
      (node (ref "R139") (pin "1") (pinfunction "1_1") (pintype "passive"))
      (node (ref "U30") (pin "25") (pinfunction "OVCUR1#_25") (pintype "passive"))
    )
    (net (code "45") (name "Net-(U30-OVCUR2#)") (class "Default")
      (node (ref "R140") (pin "1") (pinfunction "1_1") (pintype "passive"))
      (node (ref "U30") (pin "24") (pinfunction "OVCUR2#_24") (pintype "passive"))
    )
    (net (code "46") (name "Net-(U30-OVCUR3#)") (class "Default")
      (node (ref "R141") (pin "1") (pinfunction "1_1") (pintype "passive"))
      (node (ref "U30") (pin "20") (pinfunction "OVCUR3#_20") (pintype "passive"))
    )
    (net (code "47") (name "Net-(U30-OVCUR4#)") (class "Default")
      (node (ref "R142") (pin "1") (pinfunction "1_1") (pintype "passive"))
      (node (ref "U30") (pin "19") (pinfunction "OVCUR4#_19") (pintype "passive"))
    )
    (net (code "48") (name "Net-(U30-PGANG)") (class "Default")
      (node (ref "R144") (pin "1") (pinfunction "1_1") (pintype "passive"))
      (node (ref "U30") (pin "23") (pinfunction "PGANG_23") (pintype "passive"))
    )
    (net (code "49") (name "Net-(U30-PSELF)") (class "Default")
      (node (ref "R145") (pin "2") (pinfunction "2_2") (pintype "passive"))
      (node (ref "R146") (pin "1") (pinfunction "1_1") (pintype "passive"))
      (node (ref "U30") (pin "22") (pinfunction "PSELF_22") (pintype "passive"))
    )
    (net (code "50") (name "Net-(U30-PWREN#)") (class "Default")
      (node (ref "R143") (pin "1") (pinfunction "1_1") (pintype "passive"))
      (node (ref "U30") (pin "8") (pinfunction "PWREN#_8") (pintype "passive"))
    )
    (net (code "51") (name "Net-(U30-RESET#{slash}CDP)") (class "Default")
      (node (ref "R135") (pin "1") (pinfunction "1_1") (pintype "passive"))
      (node (ref "U30") (pin "17") (pinfunction "RESET#/CDP_17") (pintype "passive"))
    )
    (net (code "52") (name "Net-(U30-XI)") (class "Default")
      (node (ref "C117") (pin "2") (pinfunction "2_2") (pintype "passive"))
      (node (ref "R138") (pin "1") (pinfunction "1_1") (pintype "passive"))
      (node (ref "U30") (pin "10") (pinfunction "XI_10") (pintype "passive"))
      (node (ref "Y5") (pin "3") (pinfunction "3_3") (pintype "passive"))
    )
    (net (code "53") (name "Net-(U30-XO)") (class "Default")
      (node (ref "C119") (pin "2") (pinfunction "2_2") (pintype "passive"))
      (node (ref "R138") (pin "2") (pinfunction "2_2") (pintype "passive"))
      (node (ref "U30") (pin "11") (pinfunction "XO_11") (pintype "passive"))
      (node (ref "Y5") (pin "1") (pinfunction "1_1") (pintype "passive"))
    )
    (net (code "54") (name "Net-(U31-OVCUR1#)") (class "Default")
      (node (ref "R152") (pin "1") (pinfunction "1_1") (pintype "passive"))
      (node (ref "U31") (pin "25") (pinfunction "OVCUR1#_25") (pintype "passive"))
    )
    (net (code "55") (name "Net-(U31-OVCUR2#)") (class "Default")
      (node (ref "R154") (pin "1") (pinfunction "1_1") (pintype "passive"))
      (node (ref "U31") (pin "24") (pinfunction "OVCUR2#_24") (pintype "passive"))
    )
    (net (code "56") (name "Net-(U31-OVCUR3#)") (class "Default")
      (node (ref "R155") (pin "1") (pinfunction "1_1") (pintype "passive"))
      (node (ref "U31") (pin "20") (pinfunction "OVCUR3#_20") (pintype "passive"))
    )
    (net (code "57") (name "Net-(U31-OVCUR4#)") (class "Default")
      (node (ref "R156") (pin "1") (pinfunction "1_1") (pintype "passive"))
      (node (ref "U31") (pin "19") (pinfunction "OVCUR4#_19") (pintype "passive"))
    )
    (net (code "58") (name "Net-(U31-PGANG)") (class "Default")
      (node (ref "R158") (pin "1") (pinfunction "1_1") (pintype "passive"))
      (node (ref "U31") (pin "23") (pinfunction "PGANG_23") (pintype "passive"))
    )
    (net (code "59") (name "Net-(U31-PSELF)") (class "Default")
      (node (ref "R159") (pin "2") (pinfunction "2_2") (pintype "passive"))
      (node (ref "R160") (pin "1") (pinfunction "1_1") (pintype "passive"))
      (node (ref "U31") (pin "22") (pinfunction "PSELF_22") (pintype "passive"))
    )
    (net (code "60") (name "Net-(U31-PWREN#)") (class "Default")
      (node (ref "R157") (pin "1") (pinfunction "1_1") (pintype "passive"))
      (node (ref "U31") (pin "8") (pinfunction "PWREN#_8") (pintype "passive"))
    )
    (net (code "61") (name "Net-(U31-RESET#{slash}CDP)") (class "Default")
      (node (ref "R149") (pin "1") (pinfunction "1_1") (pintype "passive"))
      (node (ref "U31") (pin "17") (pinfunction "RESET#/CDP_17") (pintype "passive"))
    )
    (net (code "62") (name "Net-(U31-XI)") (class "Default")
      (node (ref "C131") (pin "2") (pinfunction "2_2") (pintype "passive"))
      (node (ref "R153") (pin "1") (pinfunction "1_1") (pintype "passive"))
      (node (ref "U31") (pin "10") (pinfunction "XI_10") (pintype "passive"))
      (node (ref "Y6") (pin "3") (pinfunction "3_3") (pintype "passive"))
    )
    (net (code "63") (name "Net-(U31-XO)") (class "Default")
      (node (ref "C133") (pin "2") (pinfunction "2_2") (pintype "passive"))
      (node (ref "R153") (pin "2") (pinfunction "2_2") (pintype "passive"))
      (node (ref "U31") (pin "11") (pinfunction "XO_11") (pintype "passive"))
      (node (ref "Y6") (pin "1") (pinfunction "1_1") (pintype "passive"))
    )
    (net (code "64") (name "Net-(U33-~{OC})") (class "Default")
      (node (ref "R162") (pin "1") (pinfunction "1_1") (pintype "passive"))
      (node (ref "U33") (pin "3") (pinfunction "~{OC}_3") (pintype "passive"))
    )
    (net (code "65") (name "Net-(U35-INT_N{slash}OUT3)") (class "Default")
      (node (ref "R172") (pin "1") (pinfunction "1_1") (pintype "passive"))
      (node (ref "U35") (pin "6") (pinfunction "INT_N/OUT3_6") (pintype "passive"))
    )
    (net (code "66") (name "Net-(U35-VBUS_DET)") (class "Default")
      (node (ref "R171") (pin "1") (pinfunction "1_1") (pintype "passive"))
      (node (ref "U35") (pin "4") (pinfunction "VBUS_DET_4") (pintype "passive"))
    )
    (net (code "67") (name "Net-(U35-~{EN})") (class "Default")
      (node (ref "R170") (pin "2") (pinfunction "2_2") (pintype "passive"))
      (node (ref "U35") (pin "11") (pinfunction "~{EN}_11") (pintype "passive"))
    )
    (net (code "68") (name "VDD_1V8_MAIN") (class "Default")
      (node (ref "R167") (pin "1") (pinfunction "1_1") (pintype "passive"))
    )
    (net (code "69") (name "VDD_3V3_MAIN") (class "Default")
      (node (ref "FB10") (pin "2") (pinfunction "2_2") (pintype "passive"))
      (node (ref "FB11") (pin "2") (pinfunction "2_2") (pintype "passive"))
      (node (ref "FB7") (pin "2") (pinfunction "2_2") (pintype "passive"))
      (node (ref "FB8") (pin "2") (pinfunction "2_2") (pintype "passive"))
      (node (ref "R137") (pin "2") (pinfunction "2_2") (pintype "passive"))
      (node (ref "R139") (pin "2") (pinfunction "2_2") (pintype "passive"))
      (node (ref "R140") (pin "2") (pinfunction "2_2") (pintype "passive"))
      (node (ref "R141") (pin "2") (pinfunction "2_2") (pintype "passive"))
      (node (ref "R142") (pin "2") (pinfunction "2_2") (pintype "passive"))
      (node (ref "R145") (pin "1") (pinfunction "1_1") (pintype "passive"))
      (node (ref "R151") (pin "2") (pinfunction "2_2") (pintype "passive"))
      (node (ref "R152") (pin "2") (pinfunction "2_2") (pintype "passive"))
      (node (ref "R154") (pin "2") (pinfunction "2_2") (pintype "passive"))
      (node (ref "R155") (pin "2") (pinfunction "2_2") (pintype "passive"))
      (node (ref "R156") (pin "2") (pinfunction "2_2") (pintype "passive"))
      (node (ref "R159") (pin "1") (pinfunction "1_1") (pintype "passive"))
      (node (ref "R161") (pin "1") (pinfunction "1_1") (pintype "passive"))
      (node (ref "R162") (pin "2") (pinfunction "2_2") (pintype "passive"))
      (node (ref "R169") (pin "1") (pinfunction "1_1") (pintype "passive"))
    )
    (net (code "70") (name "VDD_5V_HUB") (class "Default")
      (node (ref "C124") (pin "1") (pinfunction "1_1") (pintype "passive"))
      (node (ref "C125") (pin "1") (pinfunction "1_1") (pintype "passive"))
      (node (ref "C126") (pin "1") (pinfunction "1_1") (pintype "passive"))
      (node (ref "CON10") (pin "1") (pinfunction "1_1") (pintype "passive"))
      (node (ref "CON10") (pin "5") (pinfunction "5_5") (pintype "passive"))
      (node (ref "FB9") (pin "2") (pinfunction "2_2") (pintype "passive"))
      (node (ref "U32") (pin "5") (pinfunction "5_5") (pintype "passive"))
    )
    (net (code "71") (name "VDD_5V_MAIN") (class "Default")
      (node (ref "C142") (pin "1") (pinfunction "1_1") (pintype "passive"))
      (node (ref "FB9") (pin "1") (pinfunction "1_1") (pintype "passive"))
      (node (ref "R136") (pin "2") (pinfunction "2_2") (pintype "passive"))
      (node (ref "R150") (pin "2") (pinfunction "2_2") (pintype "passive"))
      (node (ref "U33") (pin "5") (pinfunction "IN_5") (pintype "passive"))
      (node (ref "U35") (pin "12") (pinfunction "VDD_12") (pintype "power_in"))
    )
    (net (code "72") (name "XL9555_P03{slash}USB-DRVVBUS{slash}3V3") (class "Default")
      (node (ref "R163") (pin "2") (pinfunction "2_2") (pintype "passive"))
    )
    (net (code "73") (name "unconnected-(CON11-SBU1-PadA8)") (class "Default")
      (node (ref "CON11") (pin "A8") (pinfunction "SBU1_A8") (pintype "passive+no_connect"))
    )
    (net (code "74") (name "unconnected-(CON11-SBU2-PadB8)") (class "Default")
      (node (ref "CON11") (pin "B8") (pinfunction "SBU2_B8") (pintype "passive+no_connect"))
    )
    (net (code "75") (name "unconnected-(U30-LED3{slash}SCL-Pad18)") (class "Default")
      (node (ref "U30") (pin "18") (pinfunction "LED3/SCL_18") (pintype "passive+no_connect"))
    )
    (net (code "76") (name "unconnected-(U30-LED4{slash}SDA-Pad26)") (class "Default")
      (node (ref "U30") (pin "26") (pinfunction "LED4/SDA_26") (pintype "passive+no_connect"))
    )
    (net (code "77") (name "unconnected-(U31-LED3{slash}SCL-Pad18)") (class "Default")
      (node (ref "U31") (pin "18") (pinfunction "LED3/SCL_18") (pintype "passive+no_connect"))
    )
    (net (code "78") (name "unconnected-(U31-LED4{slash}SDA-Pad26)") (class "Default")
      (node (ref "U31") (pin "26") (pinfunction "LED4/SDA_26") (pintype "passive+no_connect"))
    )
    (net (code "79") (name "unconnected-(U35-ROLE-Pad3)") (class "Default")
      (node (ref "U35") (pin "3") (pinfunction "ROLE_3") (pintype "passive+no_connect"))
    )
  )
)
